# Connectors.net
KiCad netlist of a schematic drawn in Altium Designer
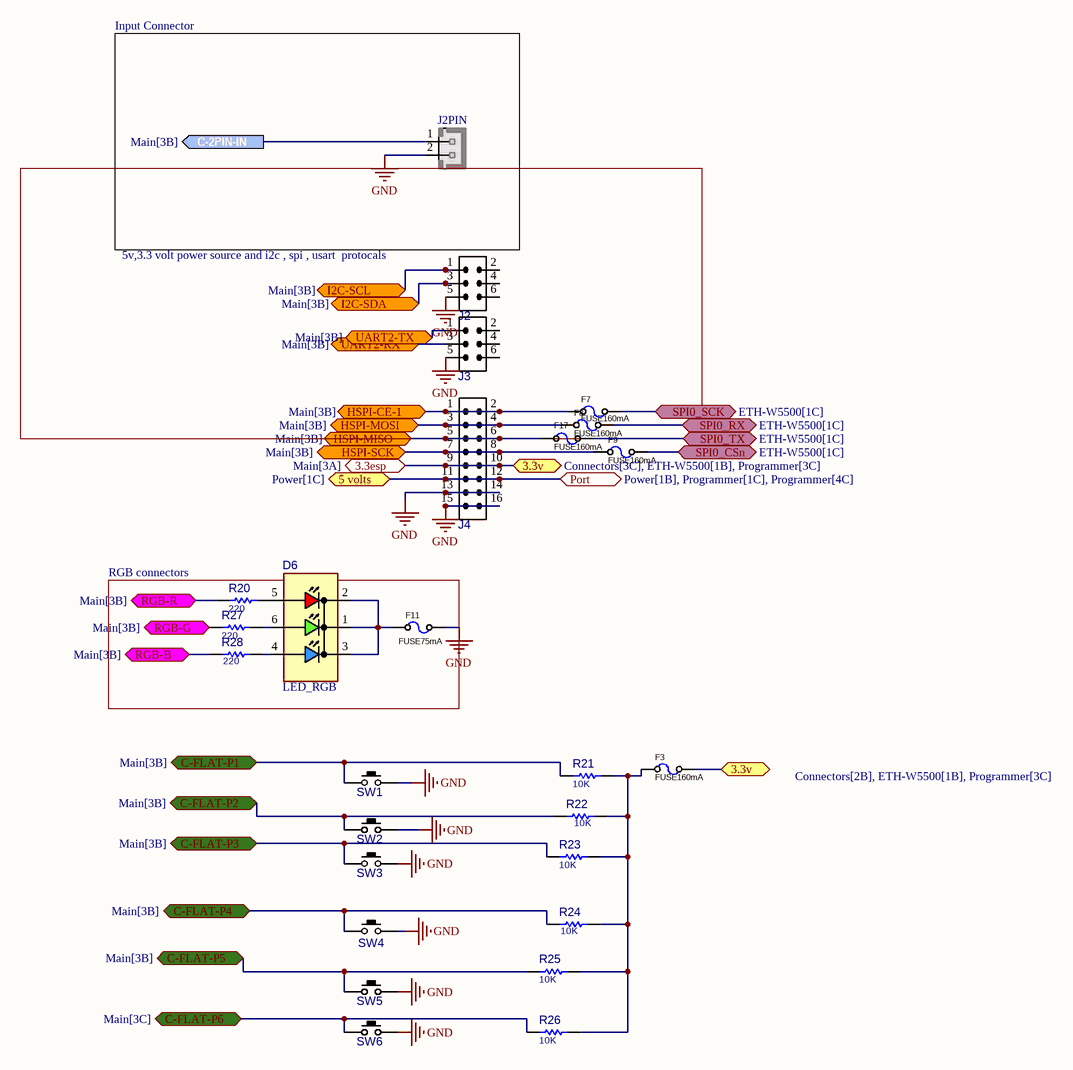
[diagram p0: Connectors.SchDoc]

(export (version "E")
  (design (tool "Eeschema 10.0.6"))
  (components
    (comp (ref "D6")
      (value "LED_RGB")
      (footprint "LED5050RGB_6")
      (description "LED, SMD, RGB COMMON CATHODE")
      (libsource (lib "led(diode)") (part "LED_SMD_RGB_5050_CC"))
    )
    (comp (ref "F3")
      (value "FUSE160mA")
      (footprint "F1206")
      (description "Fuse, 160mA, 63VDC, 1206, SMD, Fast Acting")
      (fields (field (name "MANF") "Holly Fuse") (field (name "MANF_P#") "12T-0160L"))
      (libsource (lib "protect_tvs_esd_fuse") (part "FUSE_160mA_1206"))
    )
    (comp (ref "F7")
      (value "FUSE160mA")
      (footprint "F1206")
      (description "Fuse, 160mA, 63VDC, 1206, SMD, Fast Acting")
      (fields (field (name "MANF") "Holly Fuse") (field (name "MANF_P#") "12T-0160L"))
      (libsource (lib "protect_tvs_esd_fuse") (part "FUSE_160mA_1206"))
    )
    (comp (ref "F8")
      (value "FUSE160mA")
      (footprint "F1206")
      (description "Fuse, 160mA, 63VDC, 1206, SMD, Fast Acting")
      (fields (field (name "MANF") "Holly Fuse") (field (name "MANF_P#") "12T-0160L"))
      (libsource (lib "protect_tvs_esd_fuse") (part "FUSE_160mA_1206"))
    )
    (comp (ref "F9")
      (value "FUSE160mA")
      (footprint "F1206")
      (description "Fuse, 160mA, 63VDC, 1206, SMD, Fast Acting")
      (fields (field (name "MANF") "Holly Fuse") (field (name "MANF_P#") "12T-0160L"))
      (libsource (lib "protect_tvs_esd_fuse") (part "FUSE_160mA_1206"))
    )
    (comp (ref "F11")
      (value "FUSE75mA")
      (footprint "F1206")
      (description "Fuse, 160mA, 63VDC, 1206, SMD, Fast Acting")
      (fields (field (name "MANF") "Holly Fuse") (field (name "MANF_P#") "12T-0160L"))
      (libsource (lib "protect_tvs_esd_fuse") (part "FUSE_160mA_1206"))
    )
    (comp (ref "F17")
      (value "FUSE160mA")
      (footprint "F1206")
      (description "Fuse, 160mA, 63VDC, 1206, SMD, Fast Acting")
      (fields (field (name "MANF") "Holly Fuse") (field (name "MANF_P#") "12T-0160L"))
      (libsource (lib "protect_tvs_esd_fuse") (part "FUSE_160mA_1206"))
    )
    (comp (ref "J2")
      (value "IDC_2X3")
      (footprint "IDC_2X3")
      (description "CONN, IDC, Male, pitch: 2.54mm, 6POS")
      (libsource (lib "conn_header_2.54mm_box_idc") (part "IDC_2X3"))
    )
    (comp (ref "J2PIN")
      (value "HHDR_2")
      (footprint "XH_2")
      (description "JST-XH pitch: 2.5mm")
      (libsource (lib "conn_wire2board") (part "XH_2"))
    )
    (comp (ref "J3")
      (value "IDC_2X3")
      (footprint "IDC_2X3")
      (description "CONN, IDC, Male, pitch: 2.54mm, 6POS")
      (libsource (lib "conn_header_2.54mm_box_idc") (part "IDC_2X3"))
    )
    (comp (ref "J4")
      (value "IDC_2X8")
      (footprint "IDC_2X8")
      (description "CONN, IDC, Male, pitch: 2.54mm, 16POS")
      (libsource (lib "conn_header_2.54mm_box_idc") (part "IDC_2X8"))
    )
    (comp (ref "R20")
      (value "220")
      (footprint "R0402")
      (description "RESISTOR, SMD")
      (libsource (lib "passive_smd") (part "RES_SMD"))
    )
    (comp (ref "R21")
      (value "10K")
      (footprint "R0402")
      (description "RESISTOR, SMD")
      (libsource (lib "passive_smd") (part "RES_SMD"))
    )
    (comp (ref "R22")
      (value "10K")
      (footprint "R0402")
      (description "RESISTOR, SMD")
      (libsource (lib "passive_smd") (part "RES_SMD"))
    )
    (comp (ref "R23")
      (value "10K")
      (footprint "R0402")
      (description "RESISTOR, SMD")
      (libsource (lib "passive_smd") (part "RES_SMD"))
    )
    (comp (ref "R24")
      (value "10K")
      (footprint "R0402")
      (description "RESISTOR, SMD")
      (libsource (lib "passive_smd") (part "RES_SMD"))
    )
    (comp (ref "R25")
      (value "10K")
      (footprint "R0402")
      (description "RESISTOR, SMD")
      (libsource (lib "passive_smd") (part "RES_SMD"))
    )
    (comp (ref "R26")
      (value "10K")
      (footprint "R0402")
      (description "RESISTOR, SMD")
      (libsource (lib "passive_smd") (part "RES_SMD"))
    )
    (comp (ref "R27")
      (value "220")
      (footprint "R0402")
      (description "RESISTOR, SMD")
      (libsource (lib "passive_smd") (part "RES_SMD"))
    )
    (comp (ref "R28")
      (value "220")
      (footprint "R0402")
      (description "RESISTOR, SMD")
      (libsource (lib "passive_smd") (part "RES_SMD"))
    )
    (comp (ref "SW1")
      (value "PUSHBUTTON")
      (footprint "SWPBS_SPST_6X3X5")
      (description "SWITCH, PUSH BUTTON, TACTILE, SMD, SPST, 6X3.5X4.3mm")
      (fields (field (name "MANF") "Panasonic") (field (name "MANF_P#") "EVQ-PNF04M"))
      (libsource (lib "switch_tact_PUSHB") (part "SWPBS_SPST_6X3X4"))
    )
    (comp (ref "SW2")
      (value "PUSHBUTTON")
      (footprint "SWPBS_SPST_6X3X5")
      (description "SWITCH, PUSH BUTTON, TACTILE, SMD, SPST, 6X3.5X4.3mm")
      (fields (field (name "MANF") "Panasonic") (field (name "MANF_P#") "EVQ-PNF04M"))
      (libsource (lib "switch_tact_PUSHB") (part "SWPBS_SPST_6X3X4"))
    )
    (comp (ref "SW3")
      (value "PUSHBUTTON")
      (footprint "SWPBS_SPST_6X3X5")
      (description "SWITCH, PUSH BUTTON, TACTILE, SMD, SPST, 6X3.5X4.3mm")
      (fields (field (name "MANF") "Panasonic") (field (name "MANF_P#") "EVQ-PNF04M"))
      (libsource (lib "switch_tact_PUSHB") (part "SWPBS_SPST_6X3X4"))
    )
    (comp (ref "SW4")
      (value "PUSHBUTTON")
      (footprint "SWPBS_SPST_6X3X5")
      (description "SWITCH, PUSH BUTTON, TACTILE, SMD, SPST, 6X3.5X4.3mm")
      (fields (field (name "MANF") "Panasonic") (field (name "MANF_P#") "EVQ-PNF04M"))
      (libsource (lib "switch_tact_PUSHB") (part "SWPBS_SPST_6X3X4"))
    )
    (comp (ref "SW5")
      (value "PUSHBUTTON")
      (footprint "SWPBS_SPST_6X3X5")
      (description "SWITCH, PUSH BUTTON, TACTILE, SMD, SPST, 6X3.5X4.3mm")
      (fields (field (name "MANF") "Panasonic") (field (name "MANF_P#") "EVQ-PNF04M"))
      (libsource (lib "switch_tact_PUSHB") (part "SWPBS_SPST_6X3X4"))
    )
    (comp (ref "SW6")
      (value "PUSHBUTTON")
      (footprint "SWPBS_SPST_6X3X5")
      (description "SWITCH, PUSH BUTTON, TACTILE, SMD, SPST, 6X3.5X4.3mm")
      (fields (field (name "MANF") "Panasonic") (field (name "MANF_P#") "EVQ-PNF04M"))
      (libsource (lib "switch_tact_PUSHB") (part "SWPBS_SPST_6X3X4"))
    )
  )
  (nets
    (net (code "1") (name "/3.3esp") (class "Default")
      (node (ref "F3") (pin "2") (pinfunction "2_2") (pintype "passive"))
      (node (ref "J4") (pin "10") (pinfunction "10_10") (pintype "passive"))
      (node (ref "J4") (pin "9") (pinfunction "9_9") (pintype "passive"))
    )
    (net (code "2") (name "/5 volts") (class "Default")
      (node (ref "J4") (pin "11") (pinfunction "11_11") (pintype "passive"))
      (node (ref "J4") (pin "12") (pinfunction "12_12") (pintype "passive"))
    )
    (net (code "3") (name "/C-2PIN-IN") (class "Default")
      (node (ref "J2PIN") (pin "1") (pinfunction "1_1") (pintype "passive"))
    )
    (net (code "4") (name "/C-FLAT-P1") (class "Default")
      (node (ref "R21") (pin "1") (pinfunction "1_1") (pintype "passive"))
      (node (ref "SW1") (pin "1") (pinfunction "P1_1") (pintype "passive"))
    )
    (net (code "5") (name "/C-FLAT-P2") (class "Default")
      (node (ref "R22") (pin "1") (pinfunction "1_1") (pintype "passive"))
      (node (ref "SW2") (pin "1") (pinfunction "P1_1") (pintype "passive"))
    )
    (net (code "6") (name "/C-FLAT-P3") (class "Default")
      (node (ref "R23") (pin "1") (pinfunction "1_1") (pintype "passive"))
      (node (ref "SW3") (pin "1") (pinfunction "P1_1") (pintype "passive"))
    )
    (net (code "7") (name "/C-FLAT-P4") (class "Default")
      (node (ref "R24") (pin "1") (pinfunction "1_1") (pintype "passive"))
      (node (ref "SW4") (pin "1") (pinfunction "P1_1") (pintype "passive"))
    )
    (net (code "8") (name "/C-FLAT-P5") (class "Default")
      (node (ref "R25") (pin "1") (pinfunction "1_1") (pintype "passive"))
      (node (ref "SW5") (pin "1") (pinfunction "P1_1") (pintype "passive"))
    )
    (net (code "9") (name "/C-FLAT-P6") (class "Default")
      (node (ref "R26") (pin "1") (pinfunction "1_1") (pintype "passive"))
      (node (ref "SW6") (pin "1") (pinfunction "P1_1") (pintype "passive"))
    )
    (net (code "10") (name "/HSPI-CE-1") (class "Default")
      (node (ref "F7") (pin "2") (pinfunction "2_2") (pintype "passive"))
      (node (ref "J4") (pin "1") (pinfunction "1_1") (pintype "passive"))
      (node (ref "J4") (pin "2") (pinfunction "2_2") (pintype "passive"))
    )
    (net (code "11") (name "/HSPI-MISO") (class "Default")
      (node (ref "F17") (pin "2") (pinfunction "2_2") (pintype "passive"))
      (node (ref "J4") (pin "5") (pinfunction "5_5") (pintype "passive"))
      (node (ref "J4") (pin "6") (pinfunction "6_6") (pintype "passive"))
    )
    (net (code "12") (name "/HSPI-MOSI") (class "Default")
      (node (ref "F8") (pin "2") (pinfunction "2_2") (pintype "passive"))
      (node (ref "J4") (pin "3") (pinfunction "3_3") (pintype "passive"))
      (node (ref "J4") (pin "4") (pinfunction "4_4") (pintype "passive"))
    )
    (net (code "13") (name "/HSPI-SCK") (class "Default")
      (node (ref "F9") (pin "2") (pinfunction "2_2") (pintype "passive"))
      (node (ref "J4") (pin "7") (pinfunction "7_7") (pintype "passive"))
      (node (ref "J4") (pin "8") (pinfunction "8_8") (pintype "passive"))
    )
    (net (code "14") (name "/I2C-SCL") (class "Default")
      (node (ref "J2") (pin "1") (pinfunction "1_1") (pintype "passive"))
    )
    (net (code "15") (name "/I2C-SDA") (class "Default")
      (node (ref "J2") (pin "3") (pinfunction "3_3") (pintype "passive"))
    )
    (net (code "16") (name "/RGB-B") (class "Default")
      (node (ref "R28") (pin "1") (pinfunction "1_1") (pintype "passive"))
    )
    (net (code "17") (name "/RGB-G") (class "Default")
      (node (ref "R27") (pin "1") (pinfunction "1_1") (pintype "passive"))
    )
    (net (code "18") (name "/RGB-R") (class "Default")
      (node (ref "R20") (pin "1") (pinfunction "1_1") (pintype "passive"))
    )
    (net (code "19") (name "/SPI0_CSn") (class "Default")
      (node (ref "F9") (pin "1") (pinfunction "1_1") (pintype "passive"))
    )
    (net (code "20") (name "/SPI0_RX") (class "Default")
      (node (ref "F8") (pin "1") (pinfunction "1_1") (pintype "passive"))
    )
    (net (code "21") (name "/SPI0_SCK") (class "Default")
      (node (ref "F7") (pin "1") (pinfunction "1_1") (pintype "passive"))
    )
    (net (code "22") (name "/SPI0_TX") (class "Default")
      (node (ref "F17") (pin "1") (pinfunction "1_1") (pintype "passive"))
    )
    (net (code "23") (name "/UART2-RX") (class "Default")
      (node (ref "J3") (pin "3") (pinfunction "3_3") (pintype "passive"))
    )
    (net (code "24") (name "/UART2-TX") (class "Default")
      (node (ref "J3") (pin "1") (pinfunction "1_1") (pintype "passive"))
    )
    (net (code "25") (name "GND") (class "Default")
      (node (ref "F11") (pin "2") (pinfunction "2_2") (pintype "passive"))
      (node (ref "J2") (pin "5") (pinfunction "5_5") (pintype "passive"))
      (node (ref "J2PIN") (pin "2") (pinfunction "2_2") (pintype "passive"))
      (node (ref "J3") (pin "5") (pinfunction "5_5") (pintype "passive"))
      (node (ref "J4") (pin "13") (pinfunction "13_13") (pintype "passive"))
      (node (ref "J4") (pin "14") (pinfunction "14_14") (pintype "passive"))
      (node (ref "J4") (pin "15") (pinfunction "15_15") (pintype "passive"))
      (node (ref "J4") (pin "16") (pinfunction "16_16") (pintype "passive"))
      (node (ref "SW1") (pin "2") (pinfunction "P3_2") (pintype "passive"))
      (node (ref "SW2") (pin "2") (pinfunction "P3_2") (pintype "passive"))
      (node (ref "SW3") (pin "2") (pinfunction "P3_2") (pintype "passive"))
      (node (ref "SW4") (pin "2") (pinfunction "P3_2") (pintype "passive"))
      (node (ref "SW5") (pin "2") (pinfunction "P3_2") (pintype "passive"))
      (node (ref "SW6") (pin "2") (pinfunction "P3_2") (pintype "passive"))
    )
    (net (code "26") (name "Net-(D6-AB)") (class "Default")
      (node (ref "D6") (pin "4") (pinfunction "AB_4") (pintype "passive"))
      (node (ref "R28") (pin "2") (pinfunction "2_2") (pintype "passive"))
    )
    (net (code "27") (name "Net-(D6-AG)") (class "Default")
      (node (ref "D6") (pin "5") (pinfunction "AG_5") (pintype "passive"))
      (node (ref "R20") (pin "2") (pinfunction "2_2") (pintype "passive"))
    )
    (net (code "28") (name "Net-(D6-AR)") (class "Default")
      (node (ref "D6") (pin "6") (pinfunction "AR_6") (pintype "passive"))
      (node (ref "R27") (pin "2") (pinfunction "2_2") (pintype "passive"))
    )
    (net (code "29") (name "Net-(D6-BLU)") (class "Default")
      (node (ref "D6") (pin "1") (pinfunction "RED_1") (pintype "passive"))
      (node (ref "D6") (pin "2") (pinfunction "GRN_2") (pintype "passive"))
      (node (ref "D6") (pin "3") (pinfunction "BLU_3") (pintype "passive"))
      (node (ref "F11") (pin "1") (pinfunction "1_1") (pintype "passive"))
    )
    (net (code "30") (name "Net-(F3-Pad1)") (class "Default")
      (node (ref "F3") (pin "1") (pinfunction "1_1") (pintype "passive"))
      (node (ref "R21") (pin "2") (pinfunction "2_2") (pintype "passive"))
      (node (ref "R22") (pin "2") (pinfunction "2_2") (pintype "passive"))
      (node (ref "R23") (pin "2") (pinfunction "2_2") (pintype "passive"))
      (node (ref "R24") (pin "2") (pinfunction "2_2") (pintype "passive"))
      (node (ref "R25") (pin "2") (pinfunction "2_2") (pintype "passive"))
      (node (ref "R26") (pin "2") (pinfunction "2_2") (pintype "passive"))
    )
    (net (code "31") (name "unconnected-(J2-Pad2)") (class "Default")
      (node (ref "J2") (pin "2") (pinfunction "2_2") (pintype "passive"))
    )
    (net (code "32") (name "unconnected-(J2-Pad4)") (class "Default")
      (node (ref "J2") (pin "4") (pinfunction "4_4") (pintype "passive"))
    )
    (net (code "33") (name "unconnected-(J2-Pad6)") (class "Default")
      (node (ref "J2") (pin "6") (pinfunction "6_6") (pintype "passive"))
    )
    (net (code "34") (name "unconnected-(J3-Pad2)") (class "Default")
      (node (ref "J3") (pin "2") (pinfunction "2_2") (pintype "passive"))
    )
    (net (code "35") (name "unconnected-(J3-Pad4)") (class "Default")
      (node (ref "J3") (pin "4") (pinfunction "4_4") (pintype "passive"))
    )
    (net (code "36") (name "unconnected-(J3-Pad6)") (class "Default")
      (node (ref "J3") (pin "6") (pinfunction "6_6") (pintype "passive"))
    )
  )
)
